# H2BR0-6.net
KiCad netlist of a schematic drawn in EAGLE
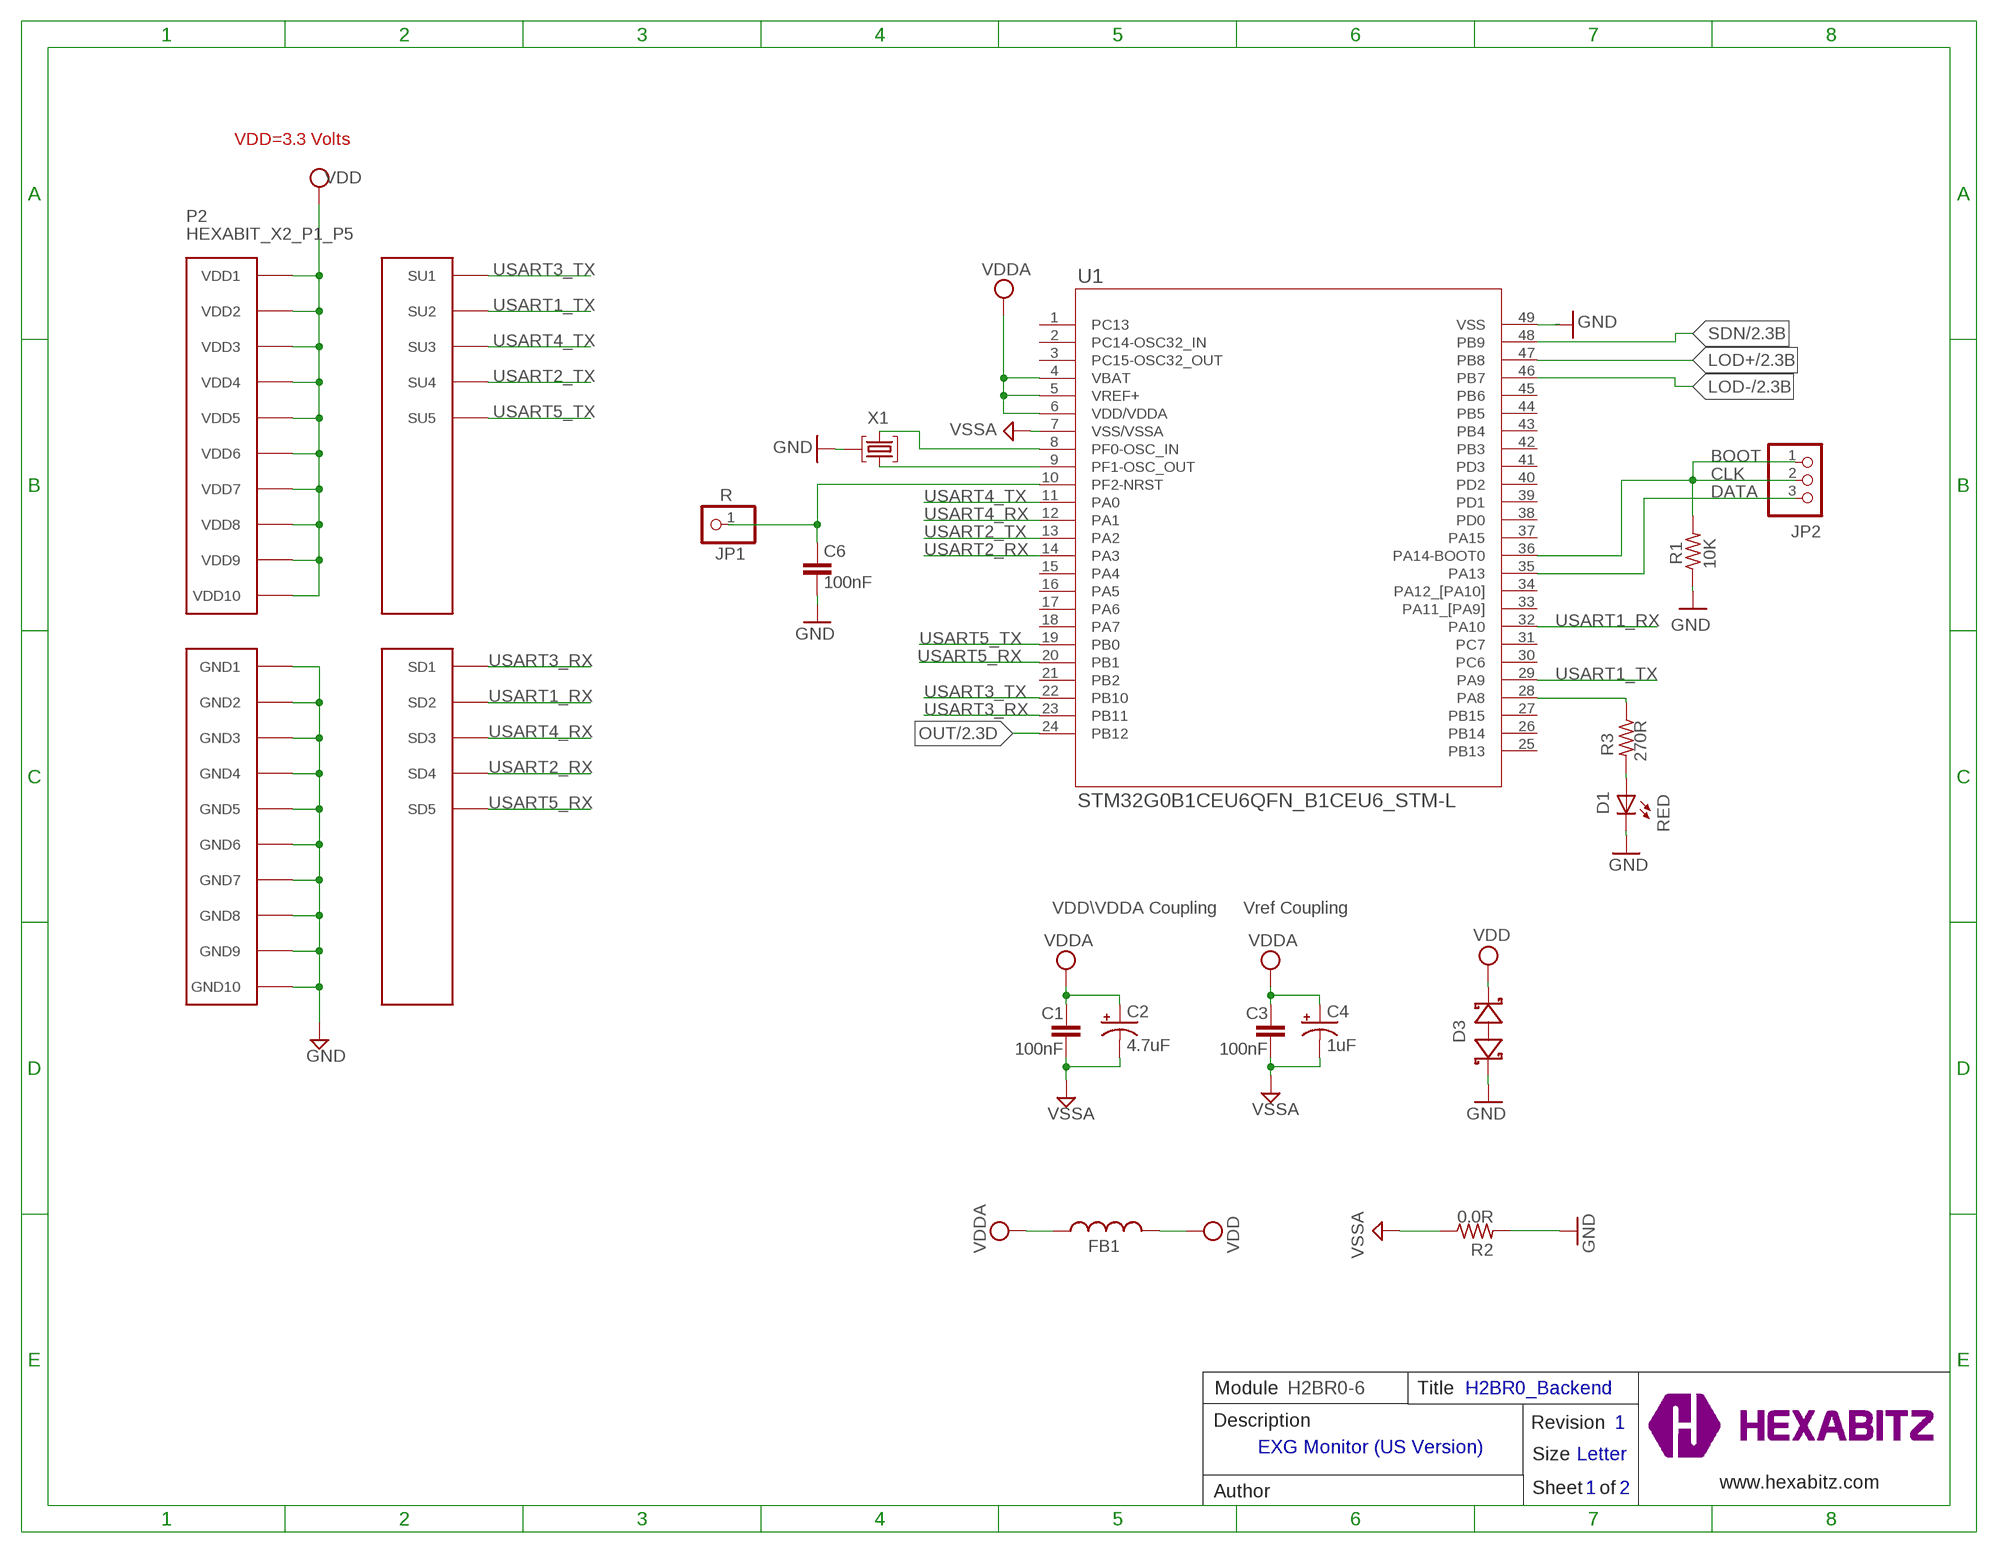
[diagram p0: schematic, sheet 1]
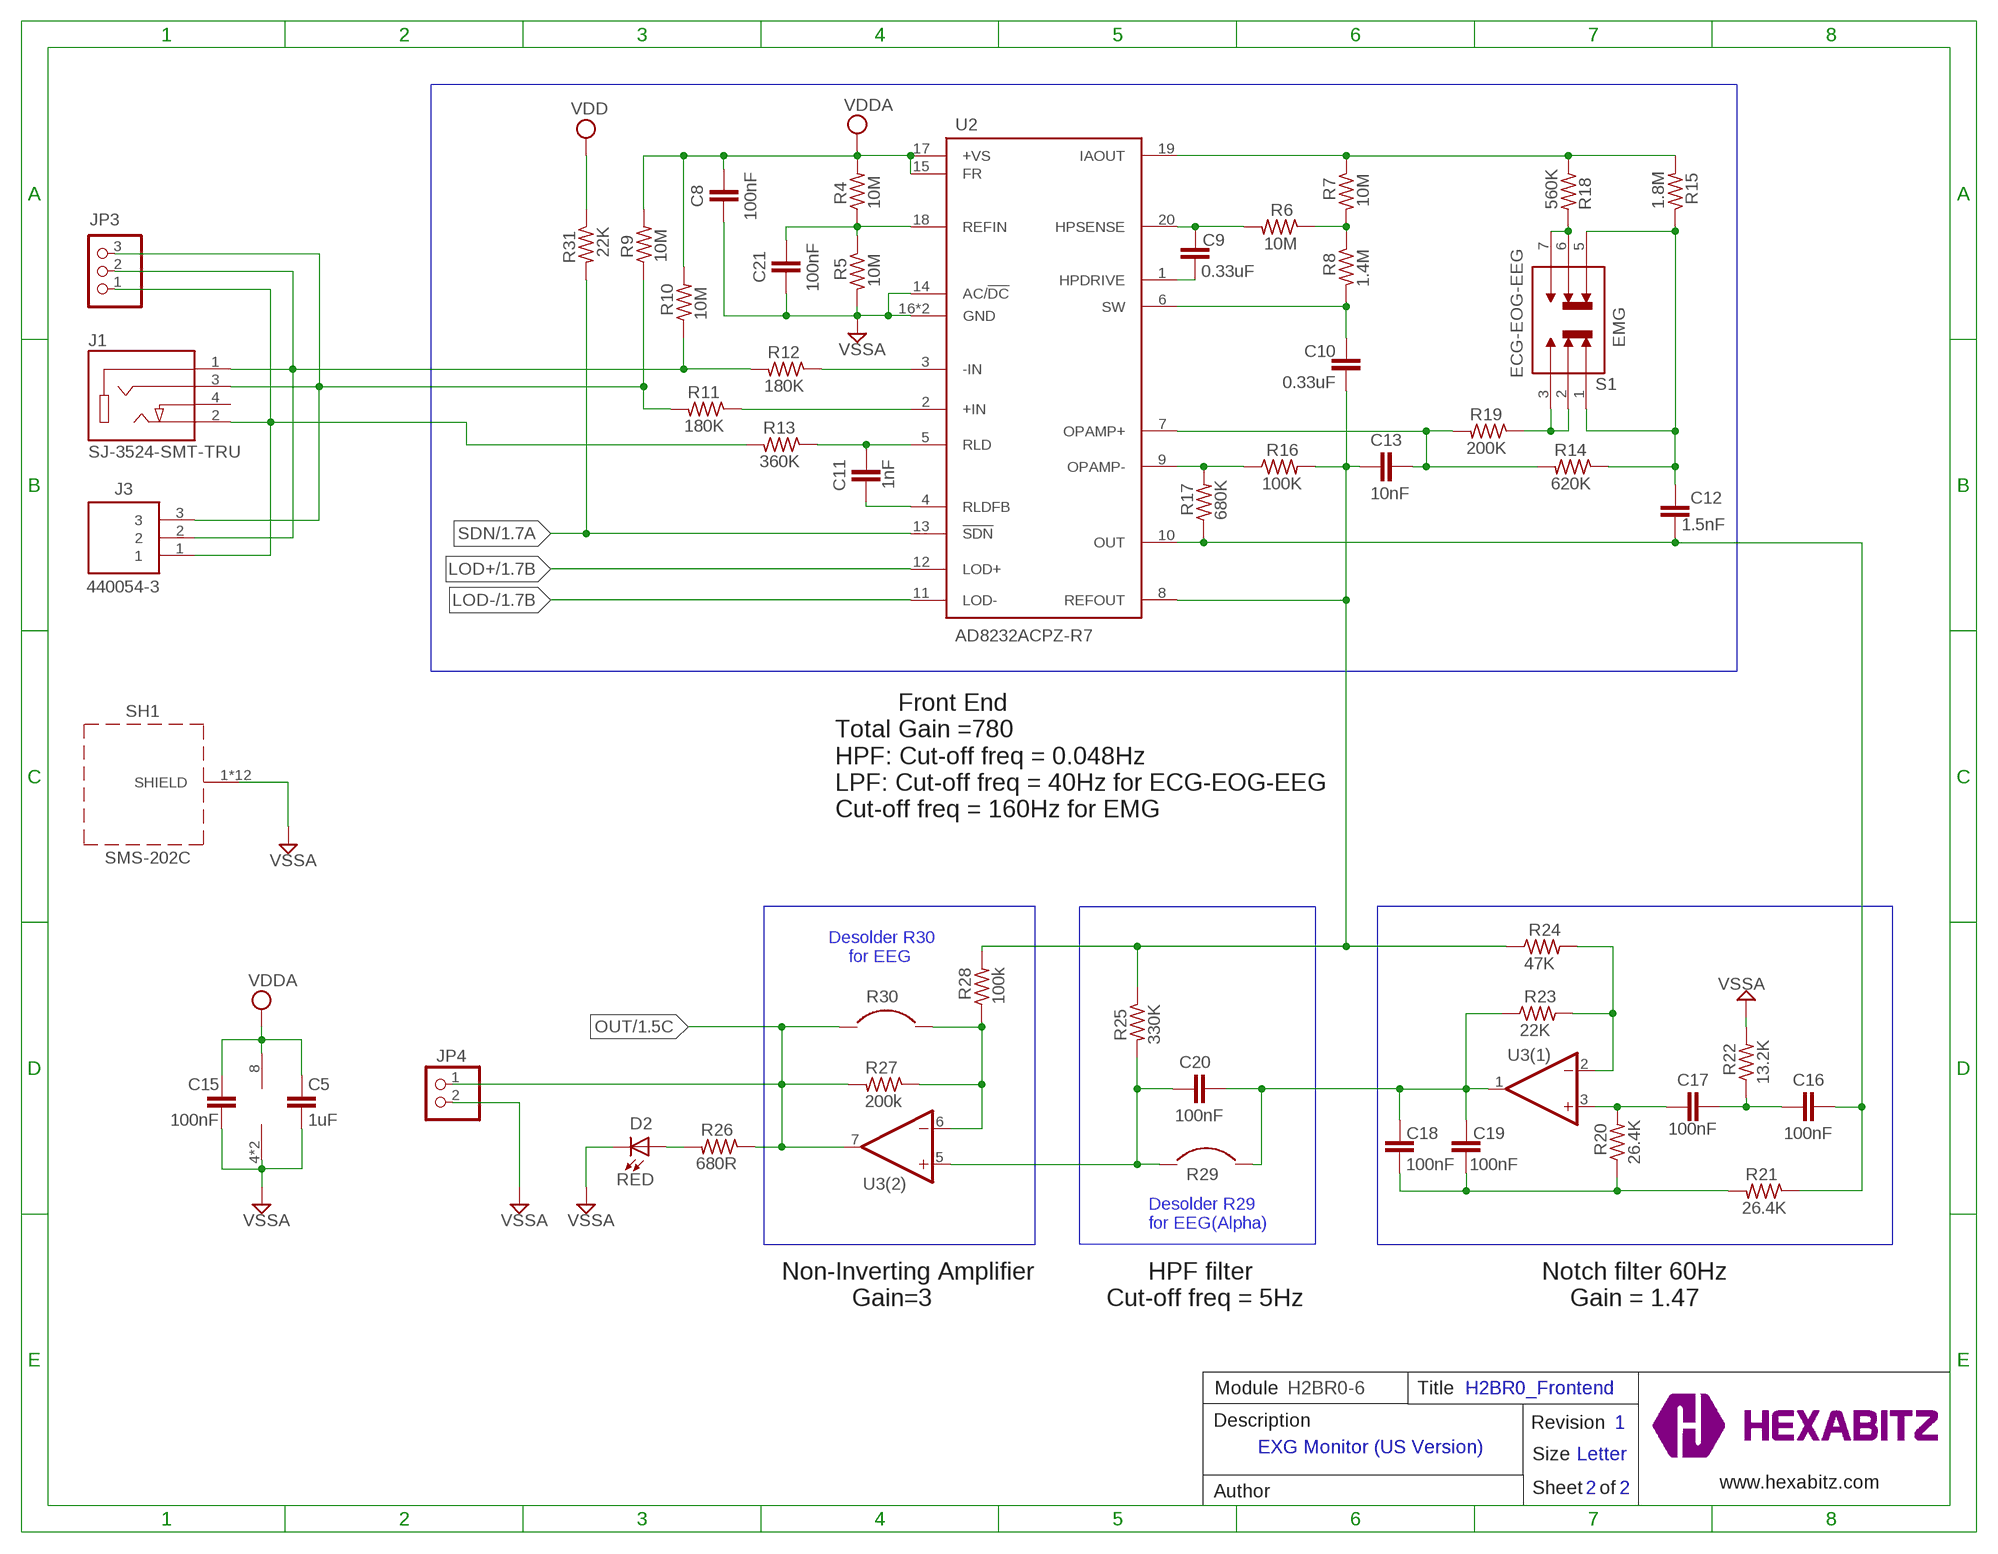
[diagram p1: schematic, sheet 2]

(export (version "E")
  (design (tool "Eeschema 10.0.6"))
  (components
    (comp (ref "C1")
      (value "100nF")
      (footprint "eagle-import:C-0603")
      (libsource (lib "eagle-import") (part "C-0603"))
    )
    (comp (ref "C2")
      (value "4.7uF")
      (footprint "eagle-import:C-0805-POL")
      (libsource (lib "eagle-import") (part "C-0805-POL"))
    )
    (comp (ref "C3")
      (value "100nF")
      (footprint "eagle-import:C-0603")
      (libsource (lib "eagle-import") (part "C-0603"))
    )
    (comp (ref "C4")
      (value "1uF")
      (footprint "eagle-import:C-0805-POL")
      (libsource (lib "eagle-import") (part "C-0805-POL"))
    )
    (comp (ref "C6")
      (value "100nF")
      (footprint "eagle-import:C-0603")
      (libsource (lib "eagle-import") (part "C-0603"))
    )
    (comp (ref "D1")
      (value "RED")
      (footprint "eagle-import:VLMS1300-GS08")
      (fields
        (field (name "MPN") "VLMS1300-GS08")
        (field (name "MFN") "Vishay")
        (field (name "MPN_1") "VLMS1300-GS08")
        (field (name "OCTOPART_URL") "https://octopart.com/vlms1300-gs08-vishay-21709201?r=sp&s=_gcP4_q8T1SC6PJQPTQ9yA")
      )
      (libsource (lib "eagle-import") (part "VLMS1300-GS08"))
    )
    (comp (ref "D3")
      (value "BOURNS_CDSOD323-T03SCBOURNS_CDSOD323-T03SC_0_0")
      (footprint "eagle-import:BOURNS_CDSOD323-T03SC_0")
      (fields (field (name "MPN") "CDSOD323-T03SC"))
      (libsource (lib "eagle-import") (part "BOURNS_CDSOD323-T03SCBOURNS_CDSOD323-T03SC_0_0"))
    )
    (comp (ref "FB1")
      (value "FB-0603")
      (footprint "eagle-import:FB-0603")
      (libsource (lib "eagle-import") (part "FB-0603"))
    )
    (comp (ref "JP1")
      (value "R")
      (footprint "eagle-import:1X01")
      (fields (field (name "MPN") "87227-1"))
      (libsource (lib "eagle-import") (part "PINHD-1X1"))
    )
    (comp (ref "JP2")
      (value "PINHD-1X3")
      (footprint "eagle-import:1X03")
      (libsource (lib "eagle-import") (part "PINHD-1X3"))
    )
    (comp (ref "P2")
      (value "HEXABIT_X2_P1_P5")
      (footprint "eagle-import:HEXABIT_17.32_X2_P1_P5")
      (libsource (lib "eagle-import") (part "HEXABIT_X2_P1_P5"))
    )
    (comp (ref "R1")
      (value "10K")
      (footprint "eagle-import:R-0603")
      (libsource (lib "eagle-import") (part "R-0603"))
    )
    (comp (ref "R2")
      (value "0.0R")
      (footprint "eagle-import:R-0603")
      (libsource (lib "eagle-import") (part "R-0603"))
    )
    (comp (ref "R3")
      (value "270R")
      (footprint "eagle-import:R-0603")
      (libsource (lib "eagle-import") (part "R-0603"))
    )
    (comp (ref "TRIMBLE-LOGO2")
      (value "HEXA-LOGO")
      (footprint "eagle-import:HEXA-LOGO")
      (libsource (lib "eagle-import") (part "HEXA-LOGO"))
    )
    (comp (ref "U1")
      (value "STM32G0B1CEU6QFN_B1CEU6_STM-L")
      (footprint "eagle-import:QFN_B1CEU6_STM-L")
      (fields
        (field (name "MANUFACTURER_PART_NUMBER") "STM32G0B1CEU6")
        (field (name "COPYRIGHT") "Copyright (C) 2021 Ultra Librarian. All rights reserved.")
      )
      (libsource (lib "eagle-import") (part "STM32G0B1CEU6QFN_B1CEU6_STM-L"))
    )
    (comp (ref "X1")
      (value "XTALL_CSTCE8M00G52")
      (footprint "eagle-import:XTALL_CSTCE8M00G52")
      (fields (field (name "MPN") "CSTCE8M00G52Z-R0"))
      (libsource (lib "eagle-import") (part "XTALL_CSTCE8M00G52"))
    )
    (comp (ref "C5")
      (value "1uF")
      (footprint "eagle-import:C-0402")
      (libsource (lib "eagle-import") (part "C-0402"))
    )
    (comp (ref "C8")
      (value "100nF")
      (footprint "eagle-import:C-0402")
      (libsource (lib "eagle-import") (part "C-0402"))
    )
    (comp (ref "C9")
      (value "0.33uF")
      (footprint "eagle-import:C-0402")
      (libsource (lib "eagle-import") (part "C-0402"))
    )
    (comp (ref "C10")
      (value "0.33uF")
      (footprint "eagle-import:C-0402")
      (libsource (lib "eagle-import") (part "C-0402"))
    )
    (comp (ref "C11")
      (value "1nF")
      (footprint "eagle-import:C-0402")
      (libsource (lib "eagle-import") (part "C-0402"))
    )
    (comp (ref "C12")
      (value "1.5nF")
      (footprint "eagle-import:C-0402")
      (libsource (lib "eagle-import") (part "C-0402"))
    )
    (comp (ref "C13")
      (value "10nF")
      (footprint "eagle-import:C-0402")
      (libsource (lib "eagle-import") (part "C-0402"))
    )
    (comp (ref "C15")
      (value "100nF")
      (footprint "eagle-import:C-0402")
      (libsource (lib "eagle-import") (part "C-0402"))
    )
    (comp (ref "C16")
      (value "100nF")
      (footprint "eagle-import:C-0402")
      (libsource (lib "eagle-import") (part "C-0402"))
    )
    (comp (ref "C17")
      (value "100nF")
      (footprint "eagle-import:C-0402")
      (libsource (lib "eagle-import") (part "C-0402"))
    )
    (comp (ref "C18")
      (value "100nF")
      (footprint "eagle-import:C-0402")
      (libsource (lib "eagle-import") (part "C-0402"))
    )
    (comp (ref "C19")
      (value "100nF")
      (footprint "eagle-import:C-0402")
      (libsource (lib "eagle-import") (part "C-0402"))
    )
    (comp (ref "C20")
      (value "100nF")
      (footprint "eagle-import:C-0402")
      (fields (field (name "MPN") "GRM188R61A105KA61J"))
      (libsource (lib "eagle-import") (part "C-0402"))
    )
    (comp (ref "C21")
      (value "100nF")
      (footprint "eagle-import:C-0402")
      (libsource (lib "eagle-import") (part "C-0402"))
    )
    (comp (ref "D2")
      (value "RED")
      (footprint "eagle-import:VLMS1300-GS08")
      (fields
        (field (name "MPN") "VLMS1300-GS08")
        (field (name "MFN") "Vishay")
        (field (name "MPN_1") "VLMS1300-GS08")
        (field (name "OCTOPART_URL") "https://octopart.com/vlms1300-gs08-vishay-21709201?r=sp&s=_gcP4_q8T1SC6PJQPTQ9yA")
      )
      (libsource (lib "eagle-import") (part "VLMS1300-GS08"))
    )
    (comp (ref "J1")
      (value "SJ-3524-SMT-TRU")
      (footprint "eagle-import:CUI_SJ-3524-SMT")
      (fields (field (name "MPN") "SJ-3524-SMT-TR"))
      (libsource (lib "eagle-import") (part "SJ-3524-SMT-TRU"))
    )
    (comp (ref "J3")
      (value "440054-3")
      (footprint "eagle-import:SHDR3W50P0X200_1X3_800X470X635")
      (fields (field (name "MOUSER_PART_NUMBER") "571-440054-3"))
      (libsource (lib "eagle-import") (part "440054-3"))
    )
    (comp (ref "JP3")
      (value "PINHD-1X3")
      (footprint "eagle-import:1X03")
      (libsource (lib "eagle-import") (part "PINHD-1X3"))
    )
    (comp (ref "JP4")
      (value "PINHD-1X2(ROUND)")
      (footprint "eagle-import:1X02")
      (libsource (lib "eagle-import") (part "PINHD-1X2(ROUND)"))
    )
    (comp (ref "R4")
      (value "10M")
      (footprint "eagle-import:R-0402")
      (libsource (lib "eagle-import") (part "R-0402"))
    )
    (comp (ref "R5")
      (value "10M")
      (footprint "eagle-import:R-0402")
      (libsource (lib "eagle-import") (part "R-0402"))
    )
    (comp (ref "R6")
      (value "10M")
      (footprint "eagle-import:R-0402")
      (libsource (lib "eagle-import") (part "R-0402"))
    )
    (comp (ref "R7")
      (value "10M")
      (footprint "eagle-import:R-0402")
      (libsource (lib "eagle-import") (part "R-0402"))
    )
    (comp (ref "R8")
      (value "1.4M")
      (footprint "eagle-import:R-0402")
      (libsource (lib "eagle-import") (part "R-0402"))
    )
    (comp (ref "R9")
      (value "10M")
      (footprint "eagle-import:R-0402")
      (libsource (lib "eagle-import") (part "R-0402"))
    )
    (comp (ref "R10")
      (value "10M")
      (footprint "eagle-import:R-0402")
      (libsource (lib "eagle-import") (part "R-0402"))
    )
    (comp (ref "R11")
      (value "180K")
      (footprint "eagle-import:R-0402")
      (libsource (lib "eagle-import") (part "R-0402"))
    )
    (comp (ref "R12")
      (value "180K")
      (footprint "eagle-import:R-0402")
      (libsource (lib "eagle-import") (part "R-0402"))
    )
    (comp (ref "R13")
      (value "360K")
      (footprint "eagle-import:R-0402")
      (libsource (lib "eagle-import") (part "R-0402"))
    )
    (comp (ref "R14")
      (value "620K")
      (footprint "eagle-import:R-0402")
      (libsource (lib "eagle-import") (part "R-0402"))
    )
    (comp (ref "R15")
      (value "1.8M")
      (footprint "eagle-import:R-0402")
      (libsource (lib "eagle-import") (part "R-0402"))
    )
    (comp (ref "R16")
      (value "100K")
      (footprint "eagle-import:R-0402")
      (libsource (lib "eagle-import") (part "R-0402"))
    )
    (comp (ref "R17")
      (value "680K")
      (footprint "eagle-import:R-0402")
      (libsource (lib "eagle-import") (part "R-0402"))
    )
    (comp (ref "R18")
      (value "560K")
      (footprint "eagle-import:R-0402")
      (libsource (lib "eagle-import") (part "R-0402"))
    )
    (comp (ref "R19")
      (value "200K")
      (footprint "eagle-import:R-0402")
      (libsource (lib "eagle-import") (part "R-0402"))
    )
    (comp (ref "R20")
      (value "26.4K")
      (footprint "eagle-import:R-0402")
      (libsource (lib "eagle-import") (part "R-0402"))
    )
    (comp (ref "R21")
      (value "26.4K")
      (footprint "eagle-import:R-0402")
      (libsource (lib "eagle-import") (part "R-0402"))
    )
    (comp (ref "R22")
      (value "13.2K")
      (footprint "eagle-import:R-0402")
      (libsource (lib "eagle-import") (part "R-0402"))
    )
    (comp (ref "R23")
      (value "22K")
      (footprint "eagle-import:R-0402")
      (libsource (lib "eagle-import") (part "R-0402"))
    )
    (comp (ref "R24")
      (value "47K")
      (footprint "eagle-import:R-0402")
      (libsource (lib "eagle-import") (part "R-0402"))
    )
    (comp (ref "R25")
      (value "330K")
      (footprint "eagle-import:R-0402")
      (libsource (lib "eagle-import") (part "R-0402"))
    )
    (comp (ref "R26")
      (value "680R")
      (footprint "eagle-import:R-0603")
      (libsource (lib "eagle-import") (part "R-0603"))
    )
    (comp (ref "R27")
      (value "200k")
      (footprint "eagle-import:R-0402")
      (libsource (lib "eagle-import") (part "R-0402"))
    )
    (comp (ref "R28")
      (value "100k")
      (footprint "eagle-import:R-0402")
      (libsource (lib "eagle-import") (part "R-0402"))
    )
    (comp (ref "R29")
      (value "SB-0603")
      (footprint "eagle-import:SB-0603")
      (libsource (lib "eagle-import") (part "SB-0603"))
    )
    (comp (ref "R30")
      (value "SB-0603")
      (footprint "eagle-import:SB-0603")
      (libsource (lib "eagle-import") (part "SB-0603"))
    )
    (comp (ref "R31")
      (value "22K")
      (footprint "eagle-import:R-0402")
      (libsource (lib "eagle-import") (part "R-0402"))
    )
    (comp (ref "S1")
      (value "JS202011JCQN")
      (footprint "eagle-import:SW_JS202011JCQN")
      (fields (field (name "MF") "C&K"))
      (libsource (lib "eagle-import") (part "JS202011JCQN"))
    )
    (comp (ref "SH1")
      (value "SMS-202C")
      (footprint "eagle-import:SMS202F")
      (fields (field (name "MOUSER_PART_NUMBER") "861-SMS-202C"))
      (libsource (lib "eagle-import") (part "SMS-202C"))
    )
    (comp (ref "U2")
      (value "AD8232ACPZ-R7")
      (footprint "eagle-import:QFN50P400X400X80-21N")
      (fields (field (name "MOUSER_PART_NUMBER") "584-AD8232ACPZ-R7"))
      (libsource (lib "eagle-import") (part "AD8232ACPZ-R7"))
    )
    (comp (ref "U3")
      (value "TSV772IQ2T_SEPARATED_SYMBOLSSON50P200X200X60-9N")
      (footprint "eagle-import:SON50P200X200X60-9N")
      (libsource (lib "eagle-import") (part "TSV772IQ2T_SEPARATED_SYMBOLSSON50P200X200X60-9N"))
    )
  )
  (nets
    (net (code "1") (name "CLK") (class "Default")
      (node (ref "JP2") (pin "1") (pinfunction "1_1") (pintype "passive"))
      (node (ref "JP2") (pin "2") (pinfunction "2_2") (pintype "passive"))
      (node (ref "R1") (pin "2") (pinfunction "2_2") (pintype "passive"))
      (node (ref "U1") (pin "36") (pinfunction "PA14-BOOT0_36") (pintype "bidirectional"))
    )
    (net (code "2") (name "DATA") (class "Default")
      (node (ref "JP2") (pin "3") (pinfunction "3_3") (pintype "passive"))
      (node (ref "U1") (pin "35") (pinfunction "PA13_35") (pintype "bidirectional"))
    )
    (net (code "3") (name "GND") (class "Default")
      (node (ref "C6") (pin "2") (pinfunction "2_2") (pintype "passive"))
      (node (ref "D1") (pin "C") (pinfunction "C_C") (pintype "passive"))
      (node (ref "D3") (pin "1") (pinfunction "A_1") (pintype "passive"))
      (node (ref "P2") (pin "PAD_PD11") (pinfunction "GND1_PAD_PD11") (pintype "power_in"))
      (node (ref "P2") (pin "PAD_PD12") (pinfunction "GND2_PAD_PD12") (pintype "power_in"))
      (node (ref "P2") (pin "PAD_PD13") (pinfunction "GND3_PAD_PD13") (pintype "power_in"))
      (node (ref "P2") (pin "PAD_PD14") (pinfunction "GND4_PAD_PD14") (pintype "power_in"))
      (node (ref "P2") (pin "PAD_PD15") (pinfunction "GND5_PAD_PD15") (pintype "power_in"))
      (node (ref "P2") (pin "PAD_PD16") (pinfunction "GND6_PAD_PD16") (pintype "power_in"))
      (node (ref "P2") (pin "PAD_PD17") (pinfunction "GND7_PAD_PD17") (pintype "power_in"))
      (node (ref "P2") (pin "PAD_PD18") (pinfunction "GND8_PAD_PD18") (pintype "power_in"))
      (node (ref "P2") (pin "PAD_PD19") (pinfunction "GND9_PAD_PD19") (pintype "power_in"))
      (node (ref "P2") (pin "PAD_PD20") (pinfunction "GND10_PAD_PD20") (pintype "power_in"))
      (node (ref "R1") (pin "1") (pinfunction "1_1") (pintype "passive"))
      (node (ref "R2") (pin "2") (pinfunction "2_2") (pintype "passive"))
      (node (ref "U1") (pin "49") (pinfunction "VSS_49") (pintype "passive"))
      (node (ref "X1") (pin "P$2") (pinfunction "2_P$2") (pintype "passive"))
    )
    (net (code "4") (name "LOD+") (class "Default")
      (node (ref "U1") (pin "47") (pinfunction "PB8_47") (pintype "bidirectional"))
      (node (ref "U2") (pin "12") (pinfunction "LOD+_12") (pintype "bidirectional"))
    )
    (net (code "5") (name "LOD-") (class "Default")
      (node (ref "U1") (pin "46") (pinfunction "PB7_46") (pintype "bidirectional"))
      (node (ref "U2") (pin "11") (pinfunction "LOD-_11") (pintype "bidirectional"))
    )
    (net (code "6") (name "Net-(C12-Pad2)") (class "Default")
      (node (ref "C12") (pin "2") (pinfunction "2_2") (pintype "passive"))
      (node (ref "R14") (pin "1") (pinfunction "1_1") (pintype "passive"))
      (node (ref "R15") (pin "1") (pinfunction "1_1") (pintype "passive"))
      (node (ref "S1") (pin "1") (pinfunction "1_1") (pintype "passive"))
      (node (ref "S1") (pin "5") (pinfunction "5_5") (pintype "passive"))
    )
    (net (code "7") (name "Net-(C16-Pad1)") (class "Default")
      (node (ref "C16") (pin "1") (pinfunction "1_1") (pintype "passive"))
      (node (ref "C17") (pin "2") (pinfunction "2_2") (pintype "passive"))
      (node (ref "R22") (pin "1") (pinfunction "1_1") (pintype "passive"))
    )
    (net (code "8") (name "Net-(C18-Pad1)") (class "Default")
      (node (ref "C18") (pin "1") (pinfunction "1_1") (pintype "passive"))
      (node (ref "C19") (pin "1") (pinfunction "1_1") (pintype "passive"))
      (node (ref "R20") (pin "1") (pinfunction "1_1") (pintype "passive"))
      (node (ref "R21") (pin "2") (pinfunction "2_2") (pintype "passive"))
    )
    (net (code "9") (name "Net-(D1-PadA)") (class "Default")
      (node (ref "D1") (pin "A") (pinfunction "A_A") (pintype "passive"))
      (node (ref "R3") (pin "2") (pinfunction "2_2") (pintype "passive"))
    )
    (net (code "10") (name "Net-(D2-PadA)") (class "Default")
      (node (ref "D2") (pin "A") (pinfunction "A_A") (pintype "passive"))
      (node (ref "R26") (pin "2") (pinfunction "2_2") (pintype "passive"))
    )
    (net (code "11") (name "Net-(J1-Pad1)") (class "Default")
      (node (ref "J1") (pin "1") (pinfunction "1_1") (pintype "passive"))
      (node (ref "J3") (pin "2") (pinfunction "2_2") (pintype "bidirectional"))
      (node (ref "JP3") (pin "2") (pinfunction "2_2") (pintype "passive"))
      (node (ref "R10") (pin "1") (pinfunction "1_1") (pintype "passive"))
      (node (ref "R12") (pin "2") (pinfunction "2_2") (pintype "passive"))
    )
    (net (code "12") (name "Net-(J1-Pad2)") (class "Default")
      (node (ref "J1") (pin "2") (pinfunction "2_2") (pintype "passive"))
      (node (ref "J3") (pin "1") (pinfunction "1_1") (pintype "bidirectional"))
      (node (ref "JP3") (pin "1") (pinfunction "1_1") (pintype "passive"))
      (node (ref "R13") (pin "2") (pinfunction "2_2") (pintype "passive"))
    )
    (net (code "13") (name "Net-(J1-Pad3)") (class "Default")
      (node (ref "J1") (pin "3") (pinfunction "3_3") (pintype "passive"))
      (node (ref "J3") (pin "3") (pinfunction "3_3") (pintype "bidirectional"))
      (node (ref "JP3") (pin "3") (pinfunction "3_3") (pintype "passive"))
      (node (ref "R11") (pin "2") (pinfunction "2_2") (pintype "passive"))
      (node (ref "R9") (pin "1") (pinfunction "1_1") (pintype "passive"))
    )
    (net (code "14") (name "Net-(R6-Pad1)") (class "Default")
      (node (ref "R6") (pin "1") (pinfunction "1_1") (pintype "passive"))
      (node (ref "R7") (pin "2") (pinfunction "2_2") (pintype "passive"))
      (node (ref "R8") (pin "1") (pinfunction "1_1") (pintype "passive"))
    )
    (net (code "15") (name "Net-(R18-Pad2)") (class "Default")
      (node (ref "R18") (pin "2") (pinfunction "2_2") (pintype "passive"))
      (node (ref "S1") (pin "6") (pinfunction "6_6") (pintype "passive"))
      (node (ref "S1") (pin "7") (pinfunction "7_7") (pintype "passive"))
    )
    (net (code "16") (name "Net-(R19-Pad1)") (class "Default")
      (node (ref "R19") (pin "1") (pinfunction "1_1") (pintype "passive"))
      (node (ref "S1") (pin "2") (pinfunction "2_2") (pintype "passive"))
      (node (ref "S1") (pin "3") (pinfunction "3_3") (pintype "passive"))
    )
    (net (code "17") (name "Net-(U1-PA8)") (class "Default")
      (node (ref "R3") (pin "1") (pinfunction "1_1") (pintype "passive"))
      (node (ref "U1") (pin "28") (pinfunction "PA8_28") (pintype "bidirectional"))
    )
    (net (code "18") (name "Net-(U1-PF0-OSC_IN)") (class "Default")
      (node (ref "U1") (pin "8") (pinfunction "PF0-OSC_IN_8") (pintype "bidirectional"))
      (node (ref "X1") (pin "P$3") (pinfunction "3_P$3") (pintype "passive"))
    )
    (net (code "19") (name "Net-(U1-PF1-OSC_OUT)") (class "Default")
      (node (ref "U1") (pin "9") (pinfunction "PF1-OSC_OUT_9") (pintype "output"))
      (node (ref "X1") (pin "P$1") (pinfunction "1_P$1") (pintype "passive"))
    )
    (net (code "20") (name "Net-(U1-PF2-NRST)") (class "Default")
      (node (ref "C6") (pin "1") (pinfunction "1_1") (pintype "passive"))
      (node (ref "JP1") (pin "1") (pinfunction "1_1") (pintype "passive"))
      (node (ref "U1") (pin "10") (pinfunction "PF2-NRST_10") (pintype "bidirectional"))
    )
    (net (code "21") (name "Net-(U2-+IN)") (class "Default")
      (node (ref "R11") (pin "1") (pinfunction "1_1") (pintype "passive"))
      (node (ref "U2") (pin "2") (pinfunction "+IN_2") (pintype "bidirectional"))
    )
    (net (code "22") (name "Net-(U2--IN)") (class "Default")
      (node (ref "R12") (pin "1") (pinfunction "1_1") (pintype "passive"))
      (node (ref "U2") (pin "3") (pinfunction "-IN_3") (pintype "bidirectional"))
    )
    (net (code "23") (name "Net-(U2-HPDRIVE)") (class "Default")
      (node (ref "C9") (pin "2") (pinfunction "2_2") (pintype "passive"))
      (node (ref "U2") (pin "1") (pinfunction "HPDRIVE_1") (pintype "bidirectional"))
    )
    (net (code "24") (name "Net-(U2-HPSENSE)") (class "Default")
      (node (ref "C9") (pin "1") (pinfunction "1_1") (pintype "passive"))
      (node (ref "R6") (pin "2") (pinfunction "2_2") (pintype "passive"))
      (node (ref "U2") (pin "20") (pinfunction "HPSENSE_20") (pintype "bidirectional"))
    )
    (net (code "25") (name "Net-(U2-IAOUT)") (class "Default")
      (node (ref "R15") (pin "2") (pinfunction "2_2") (pintype "passive"))
      (node (ref "R18") (pin "1") (pinfunction "1_1") (pintype "passive"))
      (node (ref "R7") (pin "1") (pinfunction "1_1") (pintype "passive"))
      (node (ref "U2") (pin "19") (pinfunction "IAOUT_19") (pintype "bidirectional"))
    )
    (net (code "26") (name "Net-(U2-OPAMP+)") (class "Default")
      (node (ref "C13") (pin "1") (pinfunction "1_1") (pintype "passive"))
      (node (ref "R14") (pin "2") (pinfunction "2_2") (pintype "passive"))
      (node (ref "R19") (pin "2") (pinfunction "2_2") (pintype "passive"))
      (node (ref "U2") (pin "7") (pinfunction "OPAMP+_7") (pintype "bidirectional"))
    )
    (net (code "27") (name "Net-(U2-OPAMP-)") (class "Default")
      (node (ref "R16") (pin "1") (pinfunction "1_1") (pintype "passive"))
      (node (ref "R17") (pin "2") (pinfunction "2_2") (pintype "passive"))
      (node (ref "U2") (pin "9") (pinfunction "OPAMP-_9") (pintype "bidirectional"))
    )
    (net (code "28") (name "Net-(U2-OUT)") (class "Default")
      (node (ref "C12") (pin "1") (pinfunction "1_1") (pintype "passive"))
      (node (ref "C16") (pin "2") (pinfunction "2_2") (pintype "passive"))
      (node (ref "R17") (pin "1") (pinfunction "1_1") (pintype "passive"))
      (node (ref "R21") (pin "1") (pinfunction "1_1") (pintype "passive"))
      (node (ref "U2") (pin "10") (pinfunction "OUT_10") (pintype "bidirectional"))
    )
    (net (code "29") (name "Net-(U2-REFIN)") (class "Default")
      (node (ref "C21") (pin "1") (pinfunction "1_1") (pintype "passive"))
      (node (ref "R4") (pin "1") (pinfunction "1_1") (pintype "passive"))
      (node (ref "R5") (pin "1") (pinfunction "1_1") (pintype "passive"))
      (node (ref "U2") (pin "18") (pinfunction "REFIN_18") (pintype "bidirectional"))
    )
    (net (code "30") (name "Net-(U2-REFOUT)") (class "Default")
      (node (ref "C10") (pin "2") (pinfunction "2_2") (pintype "passive"))
      (node (ref "C13") (pin "2") (pinfunction "2_2") (pintype "passive"))
      (node (ref "R16") (pin "2") (pinfunction "2_2") (pintype "passive"))
      (node (ref "R24") (pin "1") (pinfunction "1_1") (pintype "passive"))
      (node (ref "R25") (pin "1") (pinfunction "1_1") (pintype "passive"))
      (node (ref "R28") (pin "2") (pinfunction "2_2") (pintype "passive"))
      (node (ref "U2") (pin "8") (pinfunction "REFOUT_8") (pintype "bidirectional"))
    )
    (net (code "31") (name "Net-(U2-RLD)") (class "Default")
      (node (ref "C11") (pin "1") (pinfunction "1_1") (pintype "passive"))
      (node (ref "R13") (pin "1") (pinfunction "1_1") (pintype "passive"))
      (node (ref "U2") (pin "5") (pinfunction "RLD_5") (pintype "bidirectional"))
    )
    (net (code "32") (name "Net-(U2-RLDFB)") (class "Default")
      (node (ref "C11") (pin "2") (pinfunction "2_2") (pintype "passive"))
      (node (ref "U2") (pin "4") (pinfunction "RLDFB_4") (pintype "bidirectional"))
    )
    (net (code "33") (name "Net-(U2-SW)") (class "Default")
      (node (ref "C10") (pin "1") (pinfunction "1_1") (pintype "passive"))
      (node (ref "R8") (pin "2") (pinfunction "2_2") (pintype "passive"))
      (node (ref "U2") (pin "6") (pinfunction "SW_6") (pintype "bidirectional"))
    )
    (net (code "34") (name "Net-(U3A-+IN)") (class "Default")
      (node (ref "C17") (pin "1") (pinfunction "1_1") (pintype "passive"))
      (node (ref "R20") (pin "2") (pinfunction "2_2") (pintype "passive"))
      (node (ref "U3") (pin "3") (pinfunction "+IN_3") (pintype "input"))
    )
    (net (code "35") (name "Net-(U3A--IN)") (class "Default")
      (node (ref "R23") (pin "2") (pinfunction "2_2") (pintype "passive"))
      (node (ref "R24") (pin "2") (pinfunction "2_2") (pintype "passive"))
      (node (ref "U3") (pin "2") (pinfunction "-IN_2") (pintype "input"))
    )
    (net (code "36") (name "Net-(U3A-OUT)") (class "Default")
      (node (ref "C18") (pin "2") (pinfunction "2_2") (pintype "passive"))
      (node (ref "C19") (pin "2") (pinfunction "2_2") (pintype "passive"))
      (node (ref "C20") (pin "2") (pinfunction "2_2") (pintype "passive"))
      (node (ref "R23") (pin "1") (pinfunction "1_1") (pintype "passive"))
      (node (ref "R29") (pin "2") (pinfunction "2_2") (pintype "passive"))
      (node (ref "U3") (pin "1") (pinfunction "OUT_1") (pintype "output"))
    )
    (net (code "37") (name "Net-(U3B-+IN)") (class "Default")
      (node (ref "C20") (pin "1") (pinfunction "1_1") (pintype "passive"))
      (node (ref "R25") (pin "2") (pinfunction "2_2") (pintype "passive"))
      (node (ref "R29") (pin "1") (pinfunction "1_1") (pintype "passive"))
      (node (ref "U3") (pin "5") (pinfunction "+IN_5") (pintype "input"))
    )
    (net (code "38") (name "Net-(U3B--IN)") (class "Default")
      (node (ref "R27") (pin "1") (pinfunction "1_1") (pintype "passive"))
      (node (ref "R28") (pin "1") (pinfunction "1_1") (pintype "passive"))
      (node (ref "R30") (pin "2") (pinfunction "2_2") (pintype "passive"))
      (node (ref "U3") (pin "6") (pinfunction "-IN_6") (pintype "input"))
    )
    (net (code "39") (name "OUT") (class "Default")
      (node (ref "JP4") (pin "1") (pinfunction "1_1") (pintype "passive"))
      (node (ref "R26") (pin "1") (pinfunction "1_1") (pintype "passive"))
      (node (ref "R27") (pin "2") (pinfunction "2_2") (pintype "passive"))
      (node (ref "R30") (pin "1") (pinfunction "1_1") (pintype "passive"))
      (node (ref "U1") (pin "24") (pinfunction "PB12_24") (pintype "bidirectional"))
      (node (ref "U3") (pin "7") (pinfunction "OUT_7") (pintype "output"))
    )
    (net (code "40") (name "SDN") (class "Default")
      (node (ref "R31") (pin "2") (pinfunction "2_2") (pintype "passive"))
      (node (ref "U1") (pin "48") (pinfunction "PB9_48") (pintype "bidirectional"))
      (node (ref "U2") (pin "13") (pinfunction "~{SDN}_13") (pintype "bidirectional"))
    )
    (net (code "41") (name "USART1_RX") (class "Default")
      (node (ref "P2") (pin "PAD_PD2") (pinfunction "SD2_PAD_PD2") (pintype "bidirectional"))
      (node (ref "U1") (pin "32") (pinfunction "PA10_32") (pintype "bidirectional"))
    )
    (net (code "42") (name "USART1_TX") (class "Default")
      (node (ref "P2") (pin "PAD_PU2") (pinfunction "SU2_PAD_PU2") (pintype "bidirectional"))
      (node (ref "U1") (pin "29") (pinfunction "PA9_29") (pintype "bidirectional"))
    )
    (net (code "43") (name "USART2_RX") (class "Default")
      (node (ref "P2") (pin "PAD_PD4") (pinfunction "SD4_PAD_PD4") (pintype "bidirectional"))
      (node (ref "U1") (pin "14") (pinfunction "PA3_14") (pintype "bidirectional"))
    )
    (net (code "44") (name "USART2_TX") (class "Default")
      (node (ref "P2") (pin "PAD_PU4") (pinfunction "SU4_PAD_PU4") (pintype "bidirectional"))
      (node (ref "U1") (pin "13") (pinfunction "PA2_13") (pintype "bidirectional"))
    )
    (net (code "45") (name "USART3_RX") (class "Default")
      (node (ref "P2") (pin "PAD_PD1") (pinfunction "SD1_PAD_PD1") (pintype "bidirectional"))
      (node (ref "U1") (pin "23") (pinfunction "PB11_23") (pintype "bidirectional"))
    )
    (net (code "46") (name "USART3_TX") (class "Default")
      (node (ref "P2") (pin "PAD_PU1") (pinfunction "SU1_PAD_PU1") (pintype "bidirectional"))
      (node (ref "U1") (pin "22") (pinfunction "PB10_22") (pintype "bidirectional"))
    )
    (net (code "47") (name "USART4_RX") (class "Default")
      (node (ref "P2") (pin "PAD_PD3") (pinfunction "SD3_PAD_PD3") (pintype "bidirectional"))
      (node (ref "U1") (pin "12") (pinfunction "PA1_12") (pintype "bidirectional"))
    )
    (net (code "48") (name "USART4_TX") (class "Default")
      (node (ref "P2") (pin "PAD_PU3") (pinfunction "SU3_PAD_PU3") (pintype "bidirectional"))
      (node (ref "U1") (pin "11") (pinfunction "PA0_11") (pintype "bidirectional"))
    )
    (net (code "49") (name "USART5_RX") (class "Default")
      (node (ref "P2") (pin "PAD_PD5") (pinfunction "SD5_PAD_PD5") (pintype "bidirectional"))
      (node (ref "U1") (pin "20") (pinfunction "PB1_20") (pintype "bidirectional"))
    )
    (net (code "50") (name "USART5_TX") (class "Default")
      (node (ref "P2") (pin "PAD_PU5") (pinfunction "SU5_PAD_PU5") (pintype "bidirectional"))
      (node (ref "U1") (pin "19") (pinfunction "PB0_19") (pintype "bidirectional"))
    )
    (net (code "51") (name "VDD") (class "Default")
      (node (ref "D3") (pin "2") (pinfunction "C_2") (pintype "passive"))
      (node (ref "FB1") (pin "2") (pinfunction "2_2") (pintype "passive"))
      (node (ref "P2") (pin "PAD_PU11") (pinfunction "VDD1_PAD_PU11") (pintype "power_in"))
      (node (ref "P2") (pin "PAD_PU12") (pinfunction "VDD2_PAD_PU12") (pintype "power_in"))
      (node (ref "P2") (pin "PAD_PU13") (pinfunction "VDD3_PAD_PU13") (pintype "power_in"))
      (node (ref "P2") (pin "PAD_PU14") (pinfunction "VDD4_PAD_PU14") (pintype "power_in"))
      (node (ref "P2") (pin "PAD_PU15") (pinfunction "VDD5_PAD_PU15") (pintype "power_in"))
      (node (ref "P2") (pin "PAD_PU16") (pinfunction "VDD6_PAD_PU16") (pintype "power_in"))
      (node (ref "P2") (pin "PAD_PU17") (pinfunction "VDD7_PAD_PU17") (pintype "power_in"))
      (node (ref "P2") (pin "PAD_PU18") (pinfunction "VDD8_PAD_PU18") (pintype "power_in"))
      (node (ref "P2") (pin "PAD_PU19") (pinfunction "VDD9_PAD_PU19") (pintype "power_in"))
      (node (ref "P2") (pin "PAD_PU20") (pinfunction "VDD10_PAD_PU20") (pintype "power_in"))
      (node (ref "R31") (pin "1") (pinfunction "1_1") (pintype "passive"))
    )
    (net (code "52") (name "VDDA") (class "Default")
      (node (ref "C1") (pin "1") (pinfunction "1_1") (pintype "passive"))
      (node (ref "C15") (pin "1") (pinfunction "1_1") (pintype "passive"))
      (node (ref "C2") (pin "1") (pinfunction "+_1") (pintype "passive"))
      (node (ref "C3") (pin "1") (pinfunction "1_1") (pintype "passive"))
      (node (ref "C4") (pin "1") (pinfunction "+_1") (pintype "passive"))
      (node (ref "C5") (pin "1") (pinfunction "1_1") (pintype "passive"))
      (node (ref "C8") (pin "1") (pinfunction "1_1") (pintype "passive"))
      (node (ref "FB1") (pin "1") (pinfunction "1_1") (pintype "passive"))
      (node (ref "R10") (pin "2") (pinfunction "2_2") (pintype "passive"))
      (node (ref "R4") (pin "2") (pinfunction "2_2") (pintype "passive"))
      (node (ref "R9") (pin "2") (pinfunction "2_2") (pintype "passive"))
      (node (ref "U1") (pin "4") (pinfunction "VBAT_4") (pintype "passive"))
      (node (ref "U1") (pin "5") (pinfunction "VREF+_5") (pintype "power_in"))
      (node (ref "U1") (pin "6") (pinfunction "VDD/VDDA_6") (pintype "power_in"))
      (node (ref "U2") (pin "15") (pinfunction "FR_15") (pintype "bidirectional"))
      (node (ref "U2") (pin "17") (pinfunction "+VS_17") (pintype "bidirectional"))
      (node (ref "U3") (pin "8") (pinfunction "V+_8") (pintype "power_in"))
    )
    (net (code "53") (name "VSSA") (class "Default")
      (node (ref "C1") (pin "2") (pinfunction "2_2") (pintype "passive"))
      (node (ref "C15") (pin "2") (pinfunction "2_2") (pintype "passive"))
      (node (ref "C2") (pin "2") (pinfunction "-_2") (pintype "passive"))
      (node (ref "C21") (pin "2") (pinfunction "2_2") (pintype "passive"))
      (node (ref "C3") (pin "2") (pinfunction "2_2") (pintype "passive"))
      (node (ref "C4") (pin "2") (pinfunction "-_2") (pintype "passive"))
      (node (ref "C5") (pin "2") (pinfunction "2_2") (pintype "passive"))
      (node (ref "C8") (pin "2") (pinfunction "2_2") (pintype "passive"))
      (node (ref "D2") (pin "C") (pinfunction "C_C") (pintype "passive"))
      (node (ref "JP4") (pin "2") (pinfunction "2_2") (pintype "passive"))
      (node (ref "R2") (pin "1") (pinfunction "1_1") (pintype "passive"))
      (node (ref "R22") (pin "2") (pinfunction "2_2") (pintype "passive"))
      (node (ref "R5") (pin "2") (pinfunction "2_2") (pintype "passive"))
      (node (ref "SH1") (pin "1") (pinfunction "SHIELD_1") (pintype "bidirectional"))
      (node (ref "SH1") (pin "10") (pinfunction "SHIELD_10") (pintype "bidirectional"))
      (node (ref "SH1") (pin "11") (pinfunction "SHIELD_11") (pintype "bidirectional"))
      (node (ref "SH1") (pin "12") (pinfunction "SHIELD_12") (pintype "bidirectional"))
      (node (ref "SH1") (pin "2") (pinfunction "SHIELD_2") (pintype "bidirectional"))
      (node (ref "SH1") (pin "3") (pinfunction "SHIELD_3") (pintype "bidirectional"))
      (node (ref "SH1") (pin "4") (pinfunction "SHIELD_4") (pintype "bidirectional"))
      (node (ref "SH1") (pin "5") (pinfunction "SHIELD_5") (pintype "bidirectional"))
      (node (ref "SH1") (pin "6") (pinfunction "SHIELD_6") (pintype "bidirectional"))
      (node (ref "SH1") (pin "7") (pinfunction "SHIELD_7") (pintype "bidirectional"))
      (node (ref "SH1") (pin "8") (pinfunction "SHIELD_8") (pintype "bidirectional"))
      (node (ref "SH1") (pin "9") (pinfunction "SHIELD_9") (pintype "bidirectional"))
      (node (ref "U1") (pin "7") (pinfunction "VSS/VSSA_7") (pintype "passive"))
      (node (ref "U2") (pin "14") (pinfunction "AC/~{DC}_14") (pintype "bidirectional"))
      (node (ref "U2") (pin "16") (pinfunction "GND_16") (pintype "bidirectional"))
      (node (ref "U2") (pin "21") (pinfunction "GND_21") (pintype "bidirectional"))
      (node (ref "U3") (pin "4") (pinfunction "V-_4") (pintype "power_in"))
      (node (ref "U3") (pin "9") (pinfunction "V-_9") (pintype "power_in"))
    )
    (net (code "54") (name "unconnected-(J1-Pad4)") (class "Default")
      (node (ref "J1") (pin "4") (pinfunction "4_4") (pintype "passive"))
    )
    (net (code "55") (name "unconnected-(U1-PA4-Pad15)") (class "Default")
      (node (ref "U1") (pin "15") (pinfunction "PA4_15") (pintype "bidirectional"))
    )
    (net (code "56") (name "unconnected-(U1-PA5-Pad16)") (class "Default")
      (node (ref "U1") (pin "16") (pinfunction "PA5_16") (pintype "bidirectional"))
    )
    (net (code "57") (name "unconnected-(U1-PA6-Pad17)") (class "Default")
      (node (ref "U1") (pin "17") (pinfunction "PA6_17") (pintype "bidirectional"))
    )
    (net (code "58") (name "unconnected-(U1-PA7-Pad18)") (class "Default")
      (node (ref "U1") (pin "18") (pinfunction "PA7_18") (pintype "bidirectional"))
    )
    (net (code "59") (name "unconnected-(U1-PA11_[PA9]-Pad33)") (class "Default")
      (node (ref "U1") (pin "33") (pinfunction "PA11_[PA9]_33") (pintype "bidirectional"))
    )
    (net (code "60") (name "unconnected-(U1-PA12_[PA10]-Pad34)") (class "Default")
      (node (ref "U1") (pin "34") (pinfunction "PA12_[PA10]_34") (pintype "bidirectional"))
    )
    (net (code "61") (name "unconnected-(U1-PA15-Pad37)") (class "Default")
      (node (ref "U1") (pin "37") (pinfunction "PA15_37") (pintype "bidirectional"))
    )
    (net (code "62") (name "unconnected-(U1-PB2-Pad21)") (class "Default")
      (node (ref "U1") (pin "21") (pinfunction "PB2_21") (pintype "bidirectional"))
    )
    (net (code "63") (name "unconnected-(U1-PB3-Pad42)") (class "Default")
      (node (ref "U1") (pin "42") (pinfunction "PB3_42") (pintype "bidirectional"))
    )
    (net (code "64") (name "unconnected-(U1-PB4-Pad43)") (class "Default")
      (node (ref "U1") (pin "43") (pinfunction "PB4_43") (pintype "bidirectional"))
    )
    (net (code "65") (name "unconnected-(U1-PB5-Pad44)") (class "Default")
      (node (ref "U1") (pin "44") (pinfunction "PB5_44") (pintype "bidirectional"))
    )
    (net (code "66") (name "unconnected-(U1-PB6-Pad45)") (class "Default")
      (node (ref "U1") (pin "45") (pinfunction "PB6_45") (pintype "bidirectional"))
    )
    (net (code "67") (name "unconnected-(U1-PB13-Pad25)") (class "Default")
      (node (ref "U1") (pin "25") (pinfunction "PB13_25") (pintype "bidirectional"))
    )
    (net (code "68") (name "unconnected-(U1-PB14-Pad26)") (class "Default")
      (node (ref "U1") (pin "26") (pinfunction "PB14_26") (pintype "bidirectional"))
    )
    (net (code "69") (name "unconnected-(U1-PB15-Pad27)") (class "Default")
      (node (ref "U1") (pin "27") (pinfunction "PB15_27") (pintype "bidirectional"))
    )
    (net (code "70") (name "unconnected-(U1-PC6-Pad30)") (class "Default")
      (node (ref "U1") (pin "30") (pinfunction "PC6_30") (pintype "bidirectional"))
    )
    (net (code "71") (name "unconnected-(U1-PC7-Pad31)") (class "Default")
      (node (ref "U1") (pin "31") (pinfunction "PC7_31") (pintype "bidirectional"))
    )
    (net (code "72") (name "unconnected-(U1-PC13-Pad1)") (class "Default")
      (node (ref "U1") (pin "1") (pinfunction "PC13_1") (pintype "bidirectional"))
    )
    (net (code "73") (name "unconnected-(U1-PC14-OSC32_IN-Pad2)") (class "Default")
      (node (ref "U1") (pin "2") (pinfunction "PC14-OSC32_IN_2") (pintype "bidirectional"))
    )
    (net (code "74") (name "unconnected-(U1-PC15-OSC32_OUT-Pad3)") (class "Default")
      (node (ref "U1") (pin "3") (pinfunction "PC15-OSC32_OUT_3") (pintype "output"))
    )
    (net (code "75") (name "unconnected-(U1-PD0-Pad38)") (class "Default")
      (node (ref "U1") (pin "38") (pinfunction "PD0_38") (pintype "bidirectional"))
    )
    (net (code "76") (name "unconnected-(U1-PD1-Pad39)") (class "Default")
      (node (ref "U1") (pin "39") (pinfunction "PD1_39") (pintype "bidirectional"))
    )
    (net (code "77") (name "unconnected-(U1-PD2-Pad40)") (class "Default")
      (node (ref "U1") (pin "40") (pinfunction "PD2_40") (pintype "bidirectional"))
    )
    (net (code "78") (name "unconnected-(U1-PD3-Pad41)") (class "Default")
      (node (ref "U1") (pin "41") (pinfunction "PD3_41") (pintype "bidirectional"))
    )
  )
)
